# Light_Sensor_-_Teensy.net
KiCad netlist of a schematic drawn in EAGLE
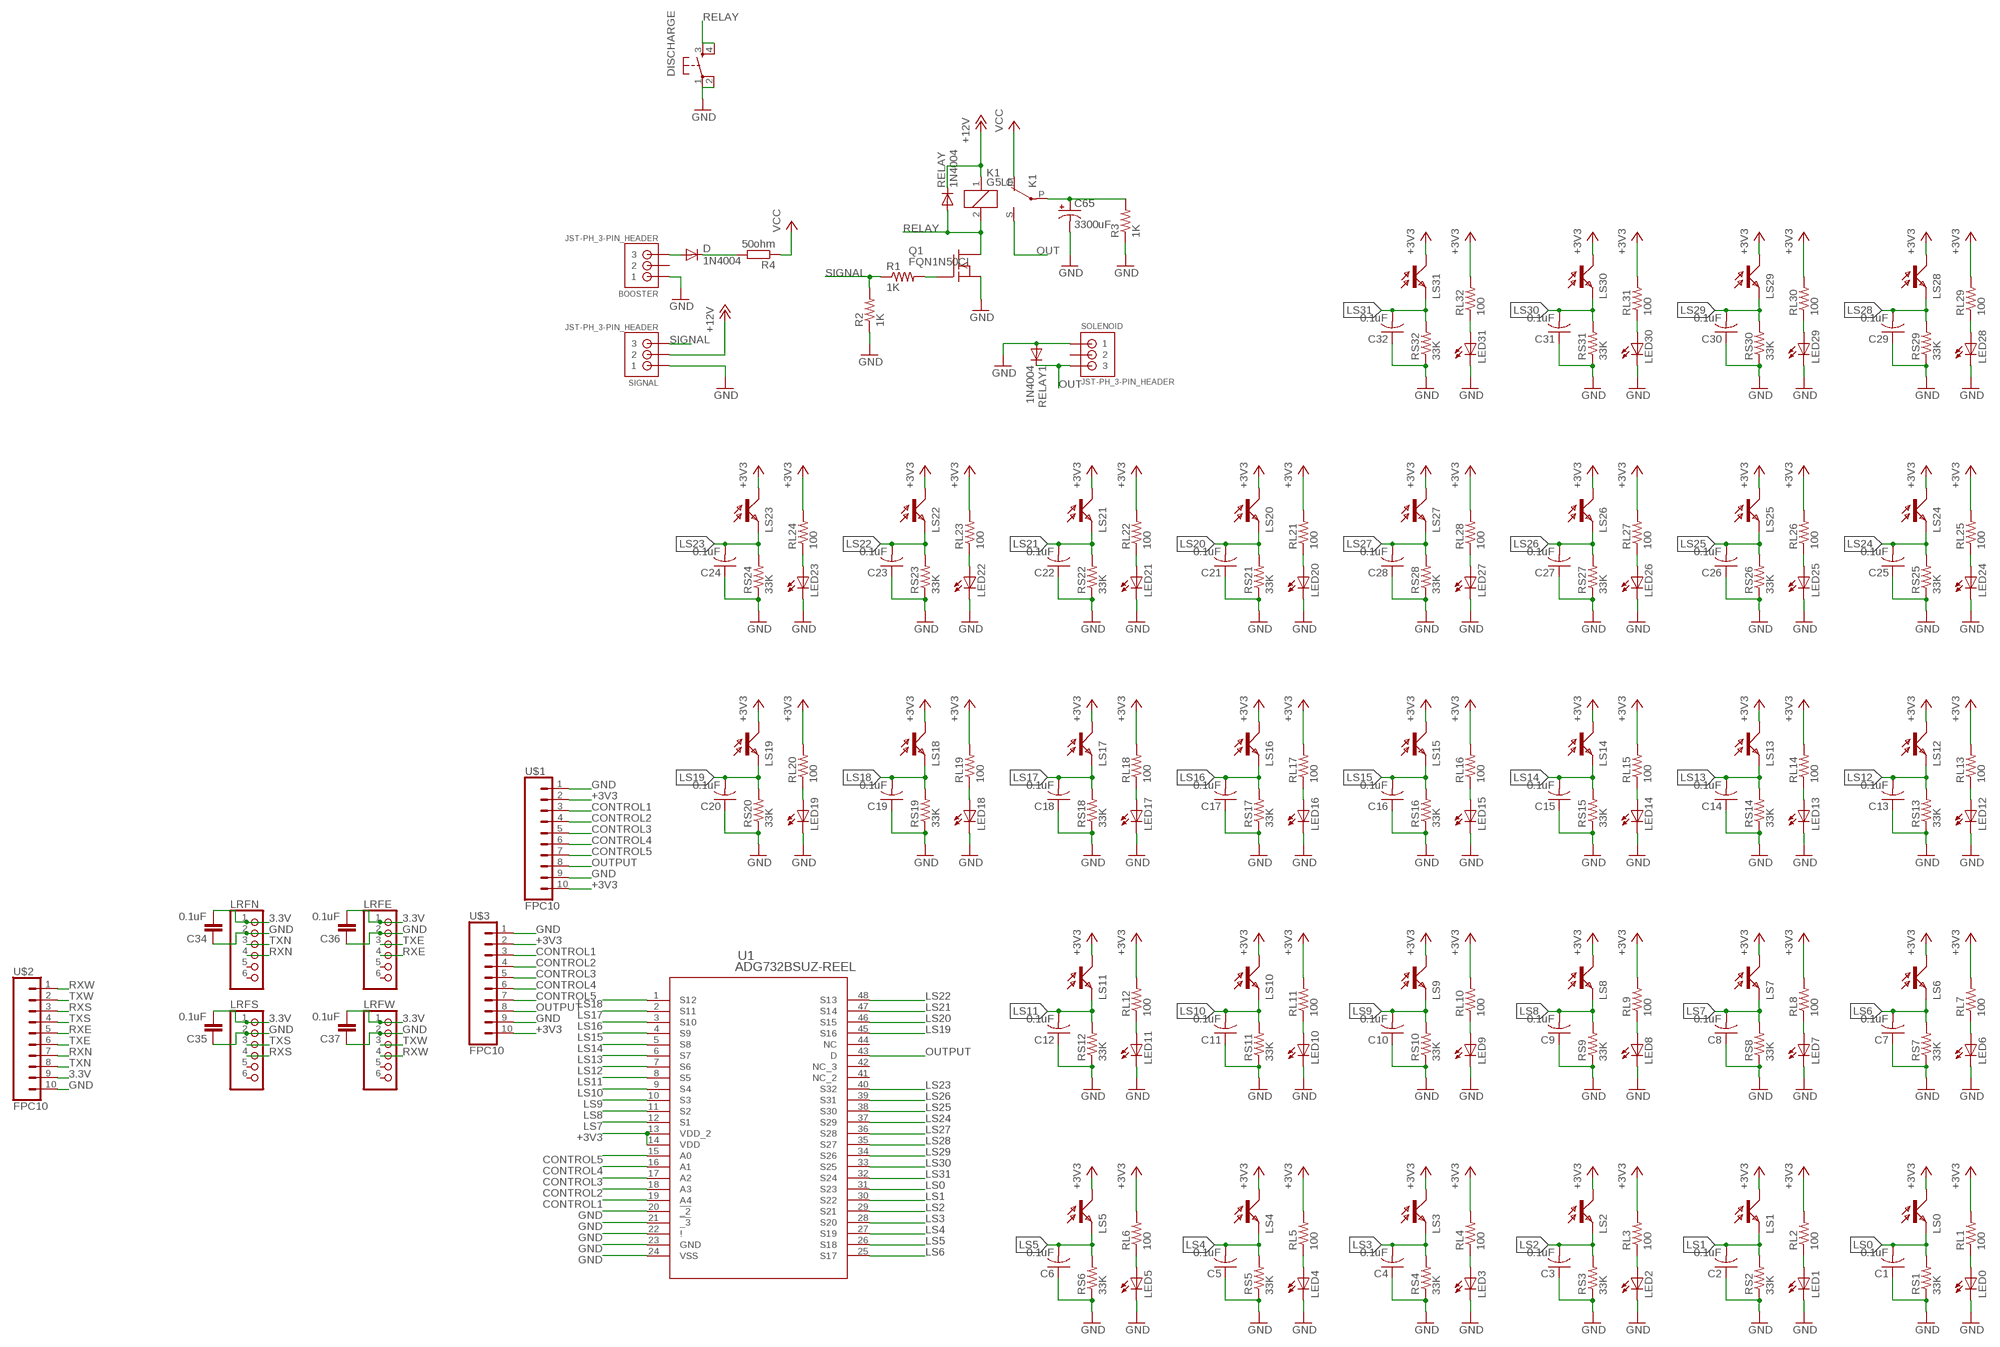
[diagram p0: schematic, sheet 1]

(export (version "E")
  (design (tool "Eeschema 10.0.6"))
  (components
    (comp (ref "BOOSTER")
      (value "JST-PH_3-PIN_HEADER")
      (footprint "eagle-import:JST_B3B-PH_HEADER")
      (libsource (lib "eagle-import") (part "JST-PH_3-PIN_HEADER"))
    )
    (comp (ref "C1")
      (value "0.1uF")
      (footprint "eagle-import:C0603")
      (libsource (lib "eagle-import") (part "C-USC0603"))
    )
    (comp (ref "C2")
      (value "0.1uF")
      (footprint "eagle-import:C0603")
      (libsource (lib "eagle-import") (part "C-USC0603"))
    )
    (comp (ref "C3")
      (value "0.1uF")
      (footprint "eagle-import:C0603")
      (libsource (lib "eagle-import") (part "C-USC0603"))
    )
    (comp (ref "C4")
      (value "0.1uF")
      (footprint "eagle-import:C0603")
      (libsource (lib "eagle-import") (part "C-USC0603"))
    )
    (comp (ref "C5")
      (value "0.1uF")
      (footprint "eagle-import:C0603")
      (libsource (lib "eagle-import") (part "C-USC0603"))
    )
    (comp (ref "C6")
      (value "0.1uF")
      (footprint "eagle-import:C0603")
      (libsource (lib "eagle-import") (part "C-USC0603"))
    )
    (comp (ref "C7")
      (value "0.1uF")
      (footprint "eagle-import:C0603")
      (libsource (lib "eagle-import") (part "C-USC0603"))
    )
    (comp (ref "C8")
      (value "0.1uF")
      (footprint "eagle-import:C0603")
      (libsource (lib "eagle-import") (part "C-USC0603"))
    )
    (comp (ref "C9")
      (value "0.1uF")
      (footprint "eagle-import:C0603")
      (libsource (lib "eagle-import") (part "C-USC0603"))
    )
    (comp (ref "C10")
      (value "0.1uF")
      (footprint "eagle-import:C0603")
      (libsource (lib "eagle-import") (part "C-USC0603"))
    )
    (comp (ref "C11")
      (value "0.1uF")
      (footprint "eagle-import:C0603")
      (libsource (lib "eagle-import") (part "C-USC0603"))
    )
    (comp (ref "C12")
      (value "0.1uF")
      (footprint "eagle-import:C0603")
      (libsource (lib "eagle-import") (part "C-USC0603"))
    )
    (comp (ref "C13")
      (value "0.1uF")
      (footprint "eagle-import:C0603")
      (libsource (lib "eagle-import") (part "C-USC0603"))
    )
    (comp (ref "C14")
      (value "0.1uF")
      (footprint "eagle-import:C0603")
      (libsource (lib "eagle-import") (part "C-USC0603"))
    )
    (comp (ref "C15")
      (value "0.1uF")
      (footprint "eagle-import:C0603")
      (libsource (lib "eagle-import") (part "C-USC0603"))
    )
    (comp (ref "C16")
      (value "0.1uF")
      (footprint "eagle-import:C0603")
      (libsource (lib "eagle-import") (part "C-USC0603"))
    )
    (comp (ref "C17")
      (value "0.1uF")
      (footprint "eagle-import:C0603")
      (libsource (lib "eagle-import") (part "C-USC0603"))
    )
    (comp (ref "C18")
      (value "0.1uF")
      (footprint "eagle-import:C0603")
      (libsource (lib "eagle-import") (part "C-USC0603"))
    )
    (comp (ref "C19")
      (value "0.1uF")
      (footprint "eagle-import:C0603")
      (libsource (lib "eagle-import") (part "C-USC0603"))
    )
    (comp (ref "C20")
      (value "0.1uF")
      (footprint "eagle-import:C0603")
      (libsource (lib "eagle-import") (part "C-USC0603"))
    )
    (comp (ref "C21")
      (value "0.1uF")
      (footprint "eagle-import:C0603")
      (libsource (lib "eagle-import") (part "C-USC0603"))
    )
    (comp (ref "C22")
      (value "0.1uF")
      (footprint "eagle-import:C0603")
      (libsource (lib "eagle-import") (part "C-USC0603"))
    )
    (comp (ref "C23")
      (value "0.1uF")
      (footprint "eagle-import:C0603")
      (libsource (lib "eagle-import") (part "C-USC0603"))
    )
    (comp (ref "C24")
      (value "0.1uF")
      (footprint "eagle-import:C0603")
      (libsource (lib "eagle-import") (part "C-USC0603"))
    )
    (comp (ref "C25")
      (value "0.1uF")
      (footprint "eagle-import:C0603")
      (libsource (lib "eagle-import") (part "C-USC0603"))
    )
    (comp (ref "C26")
      (value "0.1uF")
      (footprint "eagle-import:C0603")
      (libsource (lib "eagle-import") (part "C-USC0603"))
    )
    (comp (ref "C27")
      (value "0.1uF")
      (footprint "eagle-import:C0603")
      (libsource (lib "eagle-import") (part "C-USC0603"))
    )
    (comp (ref "C28")
      (value "0.1uF")
      (footprint "eagle-import:C0603")
      (libsource (lib "eagle-import") (part "C-USC0603"))
    )
    (comp (ref "C29")
      (value "0.1uF")
      (footprint "eagle-import:C0603")
      (libsource (lib "eagle-import") (part "C-USC0603"))
    )
    (comp (ref "C30")
      (value "0.1uF")
      (footprint "eagle-import:C0603")
      (libsource (lib "eagle-import") (part "C-USC0603"))
    )
    (comp (ref "C31")
      (value "0.1uF")
      (footprint "eagle-import:C0603")
      (libsource (lib "eagle-import") (part "C-USC0603"))
    )
    (comp (ref "C32")
      (value "0.1uF")
      (footprint "eagle-import:C0603")
      (libsource (lib "eagle-import") (part "C-USC0603"))
    )
    (comp (ref "C34")
      (value "0.1uF")
      (footprint "eagle-import:0603")
      (libsource (lib "eagle-import") (part "0.1UF-0603-25V-(+80/-20%)"))
    )
    (comp (ref "C35")
      (value "0.1uF")
      (footprint "eagle-import:0603")
      (libsource (lib "eagle-import") (part "0.1UF-0603-25V-(+80/-20%)"))
    )
    (comp (ref "C36")
      (value "0.1uF")
      (footprint "eagle-import:0603")
      (libsource (lib "eagle-import") (part "0.1UF-0603-25V-(+80/-20%)"))
    )
    (comp (ref "C37")
      (value "0.1uF")
      (footprint "eagle-import:0603")
      (libsource (lib "eagle-import") (part "0.1UF-0603-25V-(+80/-20%)"))
    )
    (comp (ref "C65")
      (value "3300uF")
      (footprint "eagle-import:EB22,5D")
      (libsource (lib "eagle-import") (part "CPOL-USE10-22.5"))
    )
    (comp (ref "D")
      (value "1N4004")
      (footprint "eagle-import:DO41-10")
      (libsource (lib "eagle-import") (part "1N4004"))
    )
    (comp (ref "DISCHARGE")
      (value "TAC_SWITCHPTH")
      (footprint "eagle-import:TACTILE-PTH")
      (libsource (lib "eagle-import") (part "TAC_SWITCHPTH"))
    )
    (comp (ref "K1")
      (value "G5LE")
      (footprint "eagle-import:G5LE")
      (libsource (lib "eagle-import") (part "G5LE"))
    )
    (comp (ref "LED0")
      (value "LEDCHIPLED_0603")
      (footprint "eagle-import:CHIPLED_0603")
      (libsource (lib "eagle-import") (part "LEDCHIPLED_0603"))
    )
    (comp (ref "LED1")
      (value "LEDCHIPLED_0603")
      (footprint "eagle-import:CHIPLED_0603")
      (libsource (lib "eagle-import") (part "LEDCHIPLED_0603"))
    )
    (comp (ref "LED2")
      (value "LEDCHIPLED_0603")
      (footprint "eagle-import:CHIPLED_0603")
      (libsource (lib "eagle-import") (part "LEDCHIPLED_0603"))
    )
    (comp (ref "LED3")
      (value "LEDCHIPLED_0603")
      (footprint "eagle-import:CHIPLED_0603")
      (libsource (lib "eagle-import") (part "LEDCHIPLED_0603"))
    )
    (comp (ref "LED4")
      (value "LEDCHIPLED_0603")
      (footprint "eagle-import:CHIPLED_0603")
      (libsource (lib "eagle-import") (part "LEDCHIPLED_0603"))
    )
    (comp (ref "LED5")
      (value "LEDCHIPLED_0603")
      (footprint "eagle-import:CHIPLED_0603")
      (libsource (lib "eagle-import") (part "LEDCHIPLED_0603"))
    )
    (comp (ref "LED6")
      (value "LEDCHIPLED_0603")
      (footprint "eagle-import:CHIPLED_0603")
      (libsource (lib "eagle-import") (part "LEDCHIPLED_0603"))
    )
    (comp (ref "LED7")
      (value "LEDCHIPLED_0603")
      (footprint "eagle-import:CHIPLED_0603")
      (libsource (lib "eagle-import") (part "LEDCHIPLED_0603"))
    )
    (comp (ref "LED8")
      (value "LEDCHIPLED_0603")
      (footprint "eagle-import:CHIPLED_0603")
      (libsource (lib "eagle-import") (part "LEDCHIPLED_0603"))
    )
    (comp (ref "LED9")
      (value "LEDCHIPLED_0603")
      (footprint "eagle-import:CHIPLED_0603")
      (libsource (lib "eagle-import") (part "LEDCHIPLED_0603"))
    )
    (comp (ref "LED10")
      (value "LEDCHIPLED_0603")
      (footprint "eagle-import:CHIPLED_0603")
      (libsource (lib "eagle-import") (part "LEDCHIPLED_0603"))
    )
    (comp (ref "LED11")
      (value "LEDCHIPLED_0603")
      (footprint "eagle-import:CHIPLED_0603")
      (libsource (lib "eagle-import") (part "LEDCHIPLED_0603"))
    )
    (comp (ref "LED12")
      (value "LEDCHIPLED_0603")
      (footprint "eagle-import:CHIPLED_0603")
      (libsource (lib "eagle-import") (part "LEDCHIPLED_0603"))
    )
    (comp (ref "LED13")
      (value "LEDCHIPLED_0603")
      (footprint "eagle-import:CHIPLED_0603")
      (libsource (lib "eagle-import") (part "LEDCHIPLED_0603"))
    )
    (comp (ref "LED14")
      (value "LEDCHIPLED_0603")
      (footprint "eagle-import:CHIPLED_0603")
      (libsource (lib "eagle-import") (part "LEDCHIPLED_0603"))
    )
    (comp (ref "LED15")
      (value "LEDCHIPLED_0603")
      (footprint "eagle-import:CHIPLED_0603")
      (libsource (lib "eagle-import") (part "LEDCHIPLED_0603"))
    )
    (comp (ref "LED16")
      (value "LEDCHIPLED_0603")
      (footprint "eagle-import:CHIPLED_0603")
      (libsource (lib "eagle-import") (part "LEDCHIPLED_0603"))
    )
    (comp (ref "LED17")
      (value "LEDCHIPLED_0603")
      (footprint "eagle-import:CHIPLED_0603")
      (libsource (lib "eagle-import") (part "LEDCHIPLED_0603"))
    )
    (comp (ref "LED18")
      (value "LEDCHIPLED_0603")
      (footprint "eagle-import:CHIPLED_0603")
      (libsource (lib "eagle-import") (part "LEDCHIPLED_0603"))
    )
    (comp (ref "LED19")
      (value "LEDCHIPLED_0603")
      (footprint "eagle-import:CHIPLED_0603")
      (libsource (lib "eagle-import") (part "LEDCHIPLED_0603"))
    )
    (comp (ref "LED20")
      (value "LEDCHIPLED_0603")
      (footprint "eagle-import:CHIPLED_0603")
      (libsource (lib "eagle-import") (part "LEDCHIPLED_0603"))
    )
    (comp (ref "LED21")
      (value "LEDCHIPLED_0603")
      (footprint "eagle-import:CHIPLED_0603")
      (libsource (lib "eagle-import") (part "LEDCHIPLED_0603"))
    )
    (comp (ref "LED22")
      (value "LEDCHIPLED_0603")
      (footprint "eagle-import:CHIPLED_0603")
      (libsource (lib "eagle-import") (part "LEDCHIPLED_0603"))
    )
    (comp (ref "LED23")
      (value "LEDCHIPLED_0603")
      (footprint "eagle-import:CHIPLED_0603")
      (libsource (lib "eagle-import") (part "LEDCHIPLED_0603"))
    )
    (comp (ref "LED24")
      (value "LEDCHIPLED_0603")
      (footprint "eagle-import:CHIPLED_0603")
      (libsource (lib "eagle-import") (part "LEDCHIPLED_0603"))
    )
    (comp (ref "LED25")
      (value "LEDCHIPLED_0603")
      (footprint "eagle-import:CHIPLED_0603")
      (libsource (lib "eagle-import") (part "LEDCHIPLED_0603"))
    )
    (comp (ref "LED26")
      (value "LEDCHIPLED_0603")
      (footprint "eagle-import:CHIPLED_0603")
      (libsource (lib "eagle-import") (part "LEDCHIPLED_0603"))
    )
    (comp (ref "LED27")
      (value "LEDCHIPLED_0603")
      (footprint "eagle-import:CHIPLED_0603")
      (libsource (lib "eagle-import") (part "LEDCHIPLED_0603"))
    )
    (comp (ref "LED28")
      (value "LEDCHIPLED_0603")
      (footprint "eagle-import:CHIPLED_0603")
      (libsource (lib "eagle-import") (part "LEDCHIPLED_0603"))
    )
    (comp (ref "LED29")
      (value "LEDCHIPLED_0603")
      (footprint "eagle-import:CHIPLED_0603")
      (libsource (lib "eagle-import") (part "LEDCHIPLED_0603"))
    )
    (comp (ref "LED30")
      (value "LEDCHIPLED_0603")
      (footprint "eagle-import:CHIPLED_0603")
      (libsource (lib "eagle-import") (part "LEDCHIPLED_0603"))
    )
    (comp (ref "LED31")
      (value "LEDCHIPLED_0603")
      (footprint "eagle-import:CHIPLED_0603")
      (libsource (lib "eagle-import") (part "LEDCHIPLED_0603"))
    )
    (comp (ref "LRFE")
      (value "PINHD-1X6")
      (footprint "eagle-import:1X06")
      (libsource (lib "eagle-import") (part "PINHD-1X6"))
    )
    (comp (ref "LRFN")
      (value "PINHD-1X6")
      (footprint "eagle-import:1X06")
      (libsource (lib "eagle-import") (part "PINHD-1X6"))
    )
    (comp (ref "LRFS")
      (value "PINHD-1X6")
      (footprint "eagle-import:1X06")
      (libsource (lib "eagle-import") (part "PINHD-1X6"))
    )
    (comp (ref "LRFW")
      (value "PINHD-1X6")
      (footprint "eagle-import:1X06")
      (libsource (lib "eagle-import") (part "PINHD-1X6"))
    )
    (comp (ref "LS0")
      (value "ALS")
      (footprint "eagle-import:SMD")
      (libsource (lib "eagle-import") (part "ALS"))
    )
    (comp (ref "LS1")
      (value "ALS")
      (footprint "eagle-import:SMD")
      (libsource (lib "eagle-import") (part "ALS"))
    )
    (comp (ref "LS2")
      (value "ALS")
      (footprint "eagle-import:SMD")
      (libsource (lib "eagle-import") (part "ALS"))
    )
    (comp (ref "LS3")
      (value "ALS")
      (footprint "eagle-import:SMD")
      (libsource (lib "eagle-import") (part "ALS"))
    )
    (comp (ref "LS4")
      (value "ALS")
      (footprint "eagle-import:SMD")
      (libsource (lib "eagle-import") (part "ALS"))
    )
    (comp (ref "LS5")
      (value "ALS")
      (footprint "eagle-import:SMD")
      (libsource (lib "eagle-import") (part "ALS"))
    )
    (comp (ref "LS6")
      (value "ALS")
      (footprint "eagle-import:SMD")
      (libsource (lib "eagle-import") (part "ALS"))
    )
    (comp (ref "LS7")
      (value "ALS")
      (footprint "eagle-import:SMD")
      (libsource (lib "eagle-import") (part "ALS"))
    )
    (comp (ref "LS8")
      (value "ALS")
      (footprint "eagle-import:SMD")
      (libsource (lib "eagle-import") (part "ALS"))
    )
    (comp (ref "LS9")
      (value "ALS")
      (footprint "eagle-import:SMD")
      (libsource (lib "eagle-import") (part "ALS"))
    )
    (comp (ref "LS10")
      (value "ALS")
      (footprint "eagle-import:SMD")
      (libsource (lib "eagle-import") (part "ALS"))
    )
    (comp (ref "LS11")
      (value "ALS")
      (footprint "eagle-import:SMD")
      (libsource (lib "eagle-import") (part "ALS"))
    )
    (comp (ref "LS12")
      (value "ALS")
      (footprint "eagle-import:SMD")
      (libsource (lib "eagle-import") (part "ALS"))
    )
    (comp (ref "LS13")
      (value "ALS")
      (footprint "eagle-import:SMD")
      (libsource (lib "eagle-import") (part "ALS"))
    )
    (comp (ref "LS14")
      (value "ALS")
      (footprint "eagle-import:SMD")
      (libsource (lib "eagle-import") (part "ALS"))
    )
    (comp (ref "LS15")
      (value "ALS")
      (footprint "eagle-import:SMD")
      (libsource (lib "eagle-import") (part "ALS"))
    )
    (comp (ref "LS16")
      (value "ALS")
      (footprint "eagle-import:SMD")
      (libsource (lib "eagle-import") (part "ALS"))
    )
    (comp (ref "LS17")
      (value "ALS")
      (footprint "eagle-import:SMD")
      (libsource (lib "eagle-import") (part "ALS"))
    )
    (comp (ref "LS18")
      (value "ALS")
      (footprint "eagle-import:SMD")
      (libsource (lib "eagle-import") (part "ALS"))
    )
    (comp (ref "LS19")
      (value "ALS")
      (footprint "eagle-import:SMD")
      (libsource (lib "eagle-import") (part "ALS"))
    )
    (comp (ref "LS20")
      (value "ALS")
      (footprint "eagle-import:SMD")
      (libsource (lib "eagle-import") (part "ALS"))
    )
    (comp (ref "LS21")
      (value "ALS")
      (footprint "eagle-import:SMD")
      (libsource (lib "eagle-import") (part "ALS"))
    )
    (comp (ref "LS22")
      (value "ALS")
      (footprint "eagle-import:SMD")
      (libsource (lib "eagle-import") (part "ALS"))
    )
    (comp (ref "LS23")
      (value "ALS")
      (footprint "eagle-import:SMD")
      (libsource (lib "eagle-import") (part "ALS"))
    )
    (comp (ref "LS24")
      (value "ALS")
      (footprint "eagle-import:SMD")
      (libsource (lib "eagle-import") (part "ALS"))
    )
    (comp (ref "LS25")
      (value "ALS")
      (footprint "eagle-import:SMD")
      (libsource (lib "eagle-import") (part "ALS"))
    )
    (comp (ref "LS26")
      (value "ALS")
      (footprint "eagle-import:SMD")
      (libsource (lib "eagle-import") (part "ALS"))
    )
    (comp (ref "LS27")
      (value "ALS")
      (footprint "eagle-import:SMD")
      (libsource (lib "eagle-import") (part "ALS"))
    )
    (comp (ref "LS28")
      (value "ALS")
      (footprint "eagle-import:SMD")
      (libsource (lib "eagle-import") (part "ALS"))
    )
    (comp (ref "LS29")
      (value "ALS")
      (footprint "eagle-import:SMD")
      (libsource (lib "eagle-import") (part "ALS"))
    )
    (comp (ref "LS30")
      (value "ALS")
      (footprint "eagle-import:SMD")
      (libsource (lib "eagle-import") (part "ALS"))
    )
    (comp (ref "LS31")
      (value "ALS")
      (footprint "eagle-import:SMD")
      (libsource (lib "eagle-import") (part "ALS"))
    )
    (comp (ref "Q1")
      (value "FQN1N50CI")
      (footprint "eagle-import:TO92-INLINE")
      (libsource (lib "eagle-import") (part "FQN1N50CI"))
    )
    (comp (ref "R1")
      (value "1K")
      (footprint "eagle-import:AXIAL-0.3")
      (libsource (lib "eagle-import") (part "1KOHM-1/4W-1%(PTH)"))
    )
    (comp (ref "R2")
      (value "1K")
      (footprint "eagle-import:AXIAL-0.3")
      (libsource (lib "eagle-import") (part "1KOHM-1/4W-1%(PTH)"))
    )
    (comp (ref "R3")
      (value "1K")
      (footprint "eagle-import:AXIAL-0.3")
      (libsource (lib "eagle-import") (part "1KOHM-1/4W-1%(PTH)"))
    )
    (comp (ref "R4")
      (value "50ohm")
      (footprint "eagle-import:0207_10")
      (libsource (lib "eagle-import") (part "R0207/10"))
    )
    (comp (ref "RELAY")
      (value "1N4004")
      (footprint "eagle-import:DO41-10")
      (libsource (lib "eagle-import") (part "1N4004"))
    )
    (comp (ref "RELAY1")
      (value "1N4004")
      (footprint "eagle-import:DO41-10")
      (libsource (lib "eagle-import") (part "1N4004"))
    )
    (comp (ref "RL1")
      (value "100")
      (footprint "eagle-import:R0603")
      (libsource (lib "eagle-import") (part "R-US_R0603"))
    )
    (comp (ref "RL2")
      (value "100")
      (footprint "eagle-import:R0603")
      (libsource (lib "eagle-import") (part "R-US_R0603"))
    )
    (comp (ref "RL3")
      (value "100")
      (footprint "eagle-import:R0603")
      (libsource (lib "eagle-import") (part "R-US_R0603"))
    )
    (comp (ref "RL4")
      (value "100")
      (footprint "eagle-import:R0603")
      (libsource (lib "eagle-import") (part "R-US_R0603"))
    )
    (comp (ref "RL5")
      (value "100")
      (footprint "eagle-import:R0603")
      (libsource (lib "eagle-import") (part "R-US_R0603"))
    )
    (comp (ref "RL6")
      (value "100")
      (footprint "eagle-import:R0603")
      (libsource (lib "eagle-import") (part "R-US_R0603"))
    )
    (comp (ref "RL7")
      (value "100")
      (footprint "eagle-import:R0603")
      (libsource (lib "eagle-import") (part "R-US_R0603"))
    )
    (comp (ref "RL8")
      (value "100")
      (footprint "eagle-import:R0603")
      (libsource (lib "eagle-import") (part "R-US_R0603"))
    )
    (comp (ref "RL9")
      (value "100")
      (footprint "eagle-import:R0603")
      (libsource (lib "eagle-import") (part "R-US_R0603"))
    )
    (comp (ref "RL10")
      (value "100")
      (footprint "eagle-import:R0603")
      (libsource (lib "eagle-import") (part "R-US_R0603"))
    )
    (comp (ref "RL11")
      (value "100")
      (footprint "eagle-import:R0603")
      (libsource (lib "eagle-import") (part "R-US_R0603"))
    )
    (comp (ref "RL12")
      (value "100")
      (footprint "eagle-import:R0603")
      (libsource (lib "eagle-import") (part "R-US_R0603"))
    )
    (comp (ref "RL13")
      (value "100")
      (footprint "eagle-import:R0603")
      (libsource (lib "eagle-import") (part "R-US_R0603"))
    )
    (comp (ref "RL14")
      (value "100")
      (footprint "eagle-import:R0603")
      (libsource (lib "eagle-import") (part "R-US_R0603"))
    )
    (comp (ref "RL15")
      (value "100")
      (footprint "eagle-import:R0603")
      (libsource (lib "eagle-import") (part "R-US_R0603"))
    )
    (comp (ref "RL16")
      (value "100")
      (footprint "eagle-import:R0603")
      (libsource (lib "eagle-import") (part "R-US_R0603"))
    )
    (comp (ref "RL17")
      (value "100")
      (footprint "eagle-import:R0603")
      (libsource (lib "eagle-import") (part "R-US_R0603"))
    )
    (comp (ref "RL18")
      (value "100")
      (footprint "eagle-import:R0603")
      (libsource (lib "eagle-import") (part "R-US_R0603"))
    )
    (comp (ref "RL19")
      (value "100")
      (footprint "eagle-import:R0603")
      (libsource (lib "eagle-import") (part "R-US_R0603"))
    )
    (comp (ref "RL20")
      (value "100")
      (footprint "eagle-import:R0603")
      (libsource (lib "eagle-import") (part "R-US_R0603"))
    )
    (comp (ref "RL21")
      (value "100")
      (footprint "eagle-import:R0603")
      (libsource (lib "eagle-import") (part "R-US_R0603"))
    )
    (comp (ref "RL22")
      (value "100")
      (footprint "eagle-import:R0603")
      (libsource (lib "eagle-import") (part "R-US_R0603"))
    )
    (comp (ref "RL23")
      (value "100")
      (footprint "eagle-import:R0603")
      (libsource (lib "eagle-import") (part "R-US_R0603"))
    )
    (comp (ref "RL24")
      (value "100")
      (footprint "eagle-import:R0603")
      (libsource (lib "eagle-import") (part "R-US_R0603"))
    )
    (comp (ref "RL25")
      (value "100")
      (footprint "eagle-import:R0603")
      (libsource (lib "eagle-import") (part "R-US_R0603"))
    )
    (comp (ref "RL26")
      (value "100")
      (footprint "eagle-import:R0603")
      (libsource (lib "eagle-import") (part "R-US_R0603"))
    )
    (comp (ref "RL27")
      (value "100")
      (footprint "eagle-import:R0603")
      (libsource (lib "eagle-import") (part "R-US_R0603"))
    )
    (comp (ref "RL28")
      (value "100")
      (footprint "eagle-import:R0603")
      (libsource (lib "eagle-import") (part "R-US_R0603"))
    )
    (comp (ref "RL29")
      (value "100")
      (footprint "eagle-import:R0603")
      (libsource (lib "eagle-import") (part "R-US_R0603"))
    )
    (comp (ref "RL30")
      (value "100")
      (footprint "eagle-import:R0603")
      (libsource (lib "eagle-import") (part "R-US_R0603"))
    )
    (comp (ref "RL31")
      (value "100")
      (footprint "eagle-import:R0603")
      (libsource (lib "eagle-import") (part "R-US_R0603"))
    )
    (comp (ref "RL32")
      (value "100")
      (footprint "eagle-import:R0603")
      (libsource (lib "eagle-import") (part "R-US_R0603"))
    )
    (comp (ref "RS1")
      (value "33K")
      (footprint "eagle-import:R0603")
      (libsource (lib "eagle-import") (part "R-US_R0603"))
    )
    (comp (ref "RS2")
      (value "33K")
      (footprint "eagle-import:R0603")
      (libsource (lib "eagle-import") (part "R-US_R0603"))
    )
    (comp (ref "RS3")
      (value "33K")
      (footprint "eagle-import:R0603")
      (libsource (lib "eagle-import") (part "R-US_R0603"))
    )
    (comp (ref "RS4")
      (value "33K")
      (footprint "eagle-import:R0603")
      (libsource (lib "eagle-import") (part "R-US_R0603"))
    )
    (comp (ref "RS5")
      (value "33K")
      (footprint "eagle-import:R0603")
      (libsource (lib "eagle-import") (part "R-US_R0603"))
    )
    (comp (ref "RS6")
      (value "33K")
      (footprint "eagle-import:R0603")
      (libsource (lib "eagle-import") (part "R-US_R0603"))
    )
    (comp (ref "RS7")
      (value "33K")
      (footprint "eagle-import:R0603")
      (libsource (lib "eagle-import") (part "R-US_R0603"))
    )
    (comp (ref "RS8")
      (value "33K")
      (footprint "eagle-import:R0603")
      (libsource (lib "eagle-import") (part "R-US_R0603"))
    )
    (comp (ref "RS9")
      (value "33K")
      (footprint "eagle-import:R0603")
      (libsource (lib "eagle-import") (part "R-US_R0603"))
    )
    (comp (ref "RS10")
      (value "33K")
      (footprint "eagle-import:R0603")
      (libsource (lib "eagle-import") (part "R-US_R0603"))
    )
    (comp (ref "RS11")
      (value "33K")
      (footprint "eagle-import:R0603")
      (libsource (lib "eagle-import") (part "R-US_R0603"))
    )
    (comp (ref "RS12")
      (value "33K")
      (footprint "eagle-import:R0603")
      (libsource (lib "eagle-import") (part "R-US_R0603"))
    )
    (comp (ref "RS13")
      (value "33K")
      (footprint "eagle-import:R0603")
      (libsource (lib "eagle-import") (part "R-US_R0603"))
    )
    (comp (ref "RS14")
      (value "33K")
      (footprint "eagle-import:R0603")
      (libsource (lib "eagle-import") (part "R-US_R0603"))
    )
    (comp (ref "RS15")
      (value "33K")
      (footprint "eagle-import:R0603")
      (libsource (lib "eagle-import") (part "R-US_R0603"))
    )
    (comp (ref "RS16")
      (value "33K")
      (footprint "eagle-import:R0603")
      (libsource (lib "eagle-import") (part "R-US_R0603"))
    )
    (comp (ref "RS17")
      (value "33K")
      (footprint "eagle-import:R0603")
      (libsource (lib "eagle-import") (part "R-US_R0603"))
    )
    (comp (ref "RS18")
      (value "33K")
      (footprint "eagle-import:R0603")
      (libsource (lib "eagle-import") (part "R-US_R0603"))
    )
    (comp (ref "RS19")
      (value "33K")
      (footprint "eagle-import:R0603")
      (libsource (lib "eagle-import") (part "R-US_R0603"))
    )
    (comp (ref "RS20")
      (value "33K")
      (footprint "eagle-import:R0603")
      (libsource (lib "eagle-import") (part "R-US_R0603"))
    )
    (comp (ref "RS21")
      (value "33K")
      (footprint "eagle-import:R0603")
      (libsource (lib "eagle-import") (part "R-US_R0603"))
    )
    (comp (ref "RS22")
      (value "33K")
      (footprint "eagle-import:R0603")
      (libsource (lib "eagle-import") (part "R-US_R0603"))
    )
    (comp (ref "RS23")
      (value "33K")
      (footprint "eagle-import:R0603")
      (libsource (lib "eagle-import") (part "R-US_R0603"))
    )
    (comp (ref "RS24")
      (value "33K")
      (footprint "eagle-import:R0603")
      (libsource (lib "eagle-import") (part "R-US_R0603"))
    )
    (comp (ref "RS25")
      (value "33K")
      (footprint "eagle-import:R0603")
      (libsource (lib "eagle-import") (part "R-US_R0603"))
    )
    (comp (ref "RS26")
      (value "33K")
      (footprint "eagle-import:R0603")
      (libsource (lib "eagle-import") (part "R-US_R0603"))
    )
    (comp (ref "RS27")
      (value "33K")
      (footprint "eagle-import:R0603")
      (libsource (lib "eagle-import") (part "R-US_R0603"))
    )
    (comp (ref "RS28")
      (value "33K")
      (footprint "eagle-import:R0603")
      (libsource (lib "eagle-import") (part "R-US_R0603"))
    )
    (comp (ref "RS29")
      (value "33K")
      (footprint "eagle-import:R0603")
      (libsource (lib "eagle-import") (part "R-US_R0603"))
    )
    (comp (ref "RS30")
      (value "33K")
      (footprint "eagle-import:R0603")
      (libsource (lib "eagle-import") (part "R-US_R0603"))
    )
    (comp (ref "RS31")
      (value "33K")
      (footprint "eagle-import:R0603")
      (libsource (lib "eagle-import") (part "R-US_R0603"))
    )
    (comp (ref "RS32")
      (value "33K")
      (footprint "eagle-import:R0603")
      (libsource (lib "eagle-import") (part "R-US_R0603"))
    )
    (comp (ref "SIGNAL")
      (value "JST-PH_3-PIN_HEADER")
      (footprint "eagle-import:JST_B3B-PH_HEADER")
      (libsource (lib "eagle-import") (part "JST-PH_3-PIN_HEADER"))
    )
    (comp (ref "SOLENOID")
      (value "JST-PH_3-PIN_HEADER")
      (footprint "eagle-import:JST_B3B-PH_HEADER")
      (libsource (lib "eagle-import") (part "JST-PH_3-PIN_HEADER"))
    )
    (comp (ref "U$1")
      (value "FPC10")
      (footprint "eagle-import:FPC10")
      (libsource (lib "eagle-import") (part "FPC10"))
    )
    (comp (ref "U$2")
      (value "FPC10")
      (footprint "eagle-import:FPC10")
      (libsource (lib "eagle-import") (part "FPC10"))
    )
    (comp (ref "U$3")
      (value "FPC10")
      (footprint "eagle-import:FPC10")
      (libsource (lib "eagle-import") (part "FPC10"))
    )
    (comp (ref "U1")
      (value "ADG732BSUZ-REEL")
      (footprint "eagle-import:SU_48")
      (fields (field (name "MANUFACTURER_PART_NUMBER") "ADG732BSUZREEL"))
      (libsource (lib "eagle-import") (part "ADG732BSUZ-REEL"))
    )
  )
  (nets
    (net (code "1") (name "+3V3") (class "Default")
      (node (ref "LS0") (pin "C") (pinfunction "C_C") (pintype "passive"))
      (node (ref "LS1") (pin "C") (pinfunction "C_C") (pintype "passive"))
      (node (ref "LS10") (pin "C") (pinfunction "C_C") (pintype "passive"))
      (node (ref "LS11") (pin "C") (pinfunction "C_C") (pintype "passive"))
      (node (ref "LS12") (pin "C") (pinfunction "C_C") (pintype "passive"))
      (node (ref "LS13") (pin "C") (pinfunction "C_C") (pintype "passive"))
      (node (ref "LS14") (pin "C") (pinfunction "C_C") (pintype "passive"))
      (node (ref "LS15") (pin "C") (pinfunction "C_C") (pintype "passive"))
      (node (ref "LS16") (pin "C") (pinfunction "C_C") (pintype "passive"))
      (node (ref "LS17") (pin "C") (pinfunction "C_C") (pintype "passive"))
      (node (ref "LS18") (pin "C") (pinfunction "C_C") (pintype "passive"))
      (node (ref "LS19") (pin "C") (pinfunction "C_C") (pintype "passive"))
      (node (ref "LS2") (pin "C") (pinfunction "C_C") (pintype "passive"))
      (node (ref "LS20") (pin "C") (pinfunction "C_C") (pintype "passive"))
      (node (ref "LS21") (pin "C") (pinfunction "C_C") (pintype "passive"))
      (node (ref "LS22") (pin "C") (pinfunction "C_C") (pintype "passive"))
      (node (ref "LS23") (pin "C") (pinfunction "C_C") (pintype "passive"))
      (node (ref "LS24") (pin "C") (pinfunction "C_C") (pintype "passive"))
      (node (ref "LS25") (pin "C") (pinfunction "C_C") (pintype "passive"))
      (node (ref "LS26") (pin "C") (pinfunction "C_C") (pintype "passive"))
      (node (ref "LS27") (pin "C") (pinfunction "C_C") (pintype "passive"))
      (node (ref "LS28") (pin "C") (pinfunction "C_C") (pintype "passive"))
      (node (ref "LS29") (pin "C") (pinfunction "C_C") (pintype "passive"))
      (node (ref "LS3") (pin "C") (pinfunction "C_C") (pintype "passive"))
      (node (ref "LS30") (pin "C") (pinfunction "C_C") (pintype "passive"))
      (node (ref "LS31") (pin "C") (pinfunction "C_C") (pintype "passive"))
      (node (ref "LS4") (pin "C") (pinfunction "C_C") (pintype "passive"))
      (node (ref "LS5") (pin "C") (pinfunction "C_C") (pintype "passive"))
      (node (ref "LS6") (pin "C") (pinfunction "C_C") (pintype "passive"))
      (node (ref "LS7") (pin "C") (pinfunction "C_C") (pintype "passive"))
      (node (ref "LS8") (pin "C") (pinfunction "C_C") (pintype "passive"))
      (node (ref "LS9") (pin "C") (pinfunction "C_C") (pintype "passive"))
      (node (ref "RL1") (pin "2") (pinfunction "2_2") (pintype "passive"))
      (node (ref "RL10") (pin "2") (pinfunction "2_2") (pintype "passive"))
      (node (ref "RL11") (pin "2") (pinfunction "2_2") (pintype "passive"))
      (node (ref "RL12") (pin "2") (pinfunction "2_2") (pintype "passive"))
      (node (ref "RL13") (pin "2") (pinfunction "2_2") (pintype "passive"))
      (node (ref "RL14") (pin "2") (pinfunction "2_2") (pintype "passive"))
      (node (ref "RL15") (pin "2") (pinfunction "2_2") (pintype "passive"))
      (node (ref "RL16") (pin "2") (pinfunction "2_2") (pintype "passive"))
      (node (ref "RL17") (pin "2") (pinfunction "2_2") (pintype "passive"))
      (node (ref "RL18") (pin "2") (pinfunction "2_2") (pintype "passive"))
      (node (ref "RL19") (pin "2") (pinfunction "2_2") (pintype "passive"))
      (node (ref "RL2") (pin "2") (pinfunction "2_2") (pintype "passive"))
      (node (ref "RL20") (pin "2") (pinfunction "2_2") (pintype "passive"))
      (node (ref "RL21") (pin "2") (pinfunction "2_2") (pintype "passive"))
      (node (ref "RL22") (pin "2") (pinfunction "2_2") (pintype "passive"))
      (node (ref "RL23") (pin "2") (pinfunction "2_2") (pintype "passive"))
      (node (ref "RL24") (pin "2") (pinfunction "2_2") (pintype "passive"))
      (node (ref "RL25") (pin "2") (pinfunction "2_2") (pintype "passive"))
      (node (ref "RL26") (pin "2") (pinfunction "2_2") (pintype "passive"))
      (node (ref "RL27") (pin "2") (pinfunction "2_2") (pintype "passive"))
      (node (ref "RL28") (pin "2") (pinfunction "2_2") (pintype "passive"))
      (node (ref "RL29") (pin "2") (pinfunction "2_2") (pintype "passive"))
      (node (ref "RL3") (pin "2") (pinfunction "2_2") (pintype "passive"))
      (node (ref "RL30") (pin "2") (pinfunction "2_2") (pintype "passive"))
      (node (ref "RL31") (pin "2") (pinfunction "2_2") (pintype "passive"))
      (node (ref "RL32") (pin "2") (pinfunction "2_2") (pintype "passive"))
      (node (ref "RL4") (pin "2") (pinfunction "2_2") (pintype "passive"))
      (node (ref "RL5") (pin "2") (pinfunction "2_2") (pintype "passive"))
      (node (ref "RL6") (pin "2") (pinfunction "2_2") (pintype "passive"))
      (node (ref "RL7") (pin "2") (pinfunction "2_2") (pintype "passive"))
      (node (ref "RL8") (pin "2") (pinfunction "2_2") (pintype "passive"))
      (node (ref "RL9") (pin "2") (pinfunction "2_2") (pintype "passive"))
      (node (ref "U$1") (pin "10") (pinfunction "10_10") (pintype "passive"))
      (node (ref "U$1") (pin "2") (pinfunction "2_2") (pintype "passive"))
      (node (ref "U$3") (pin "10") (pinfunction "10_10") (pintype "passive"))
      (node (ref "U$3") (pin "2") (pinfunction "2_2") (pintype "passive"))
      (node (ref "U1") (pin "13") (pinfunction "VDD_2_13") (pintype "power_in"))
      (node (ref "U1") (pin "14") (pinfunction "VDD_14") (pintype "power_in"))
    )
    (net (code "2") (name "+12V") (class "Default")
      (node (ref "K1") (pin "1") (pinfunction "1_1") (pintype "passive"))
      (node (ref "RELAY") (pin "C") (pinfunction "C_C") (pintype "passive"))
      (node (ref "SIGNAL") (pin "P2") (pinfunction "2_P2") (pintype "bidirectional"))
    )
    (net (code "3") (name "/3.3V") (class "Default")
      (node (ref "C34") (pin "2") (pinfunction "2_2") (pintype "passive"))
      (node (ref "C35") (pin "2") (pinfunction "2_2") (pintype "passive"))
      (node (ref "C36") (pin "2") (pinfunction "2_2") (pintype "passive"))
      (node (ref "C37") (pin "2") (pinfunction "2_2") (pintype "passive"))
      (node (ref "LRFE") (pin "1") (pinfunction "1_1") (pintype "passive"))
      (node (ref "LRFN") (pin "1") (pinfunction "1_1") (pintype "passive"))
      (node (ref "LRFS") (pin "1") (pinfunction "1_1") (pintype "passive"))
      (node (ref "LRFW") (pin "1") (pinfunction "1_1") (pintype "passive"))
      (node (ref "U$2") (pin "9") (pinfunction "9_9") (pintype "passive"))
    )
    (net (code "4") (name "/CONTROL1") (class "Default")
      (node (ref "U$1") (pin "3") (pinfunction "3_3") (pintype "passive"))
      (node (ref "U$3") (pin "3") (pinfunction "3_3") (pintype "passive"))
      (node (ref "U1") (pin "19") (pinfunction "A4_19") (pintype "passive"))
    )
    (net (code "5") (name "/CONTROL2") (class "Default")
      (node (ref "U$1") (pin "4") (pinfunction "4_4") (pintype "passive"))
      (node (ref "U$3") (pin "4") (pinfunction "4_4") (pintype "passive"))
      (node (ref "U1") (pin "18") (pinfunction "A3_18") (pintype "passive"))
    )
    (net (code "6") (name "/CONTROL3") (class "Default")
      (node (ref "U$1") (pin "5") (pinfunction "5_5") (pintype "passive"))
      (node (ref "U$3") (pin "5") (pinfunction "5_5") (pintype "passive"))
      (node (ref "U1") (pin "17") (pinfunction "A2_17") (pintype "passive"))
    )
    (net (code "7") (name "/CONTROL4") (class "Default")
      (node (ref "U$1") (pin "6") (pinfunction "6_6") (pintype "passive"))
      (node (ref "U$3") (pin "6") (pinfunction "6_6") (pintype "passive"))
      (node (ref "U1") (pin "16") (pinfunction "A1_16") (pintype "passive"))
    )
    (net (code "8") (name "/CONTROL5") (class "Default")
      (node (ref "U$1") (pin "7") (pinfunction "7_7") (pintype "passive"))
      (node (ref "U$3") (pin "7") (pinfunction "7_7") (pintype "passive"))
      (node (ref "U1") (pin "15") (pinfunction "A0_15") (pintype "passive"))
    )
    (net (code "9") (name "/OUT") (class "Default")
      (node (ref "K1") (pin "S") (pinfunction "S_S") (pintype "passive"))
      (node (ref "RELAY1") (pin "C") (pinfunction "C_C") (pintype "passive"))
      (node (ref "SOLENOID") (pin "P3") (pinfunction "3_P3") (pintype "bidirectional"))
    )
    (net (code "10") (name "/OUTPUT") (class "Default")
      (node (ref "U$1") (pin "8") (pinfunction "8_8") (pintype "passive"))
      (node (ref "U$3") (pin "8") (pinfunction "8_8") (pintype "passive"))
      (node (ref "U1") (pin "43") (pinfunction "D_43") (pintype "passive"))
    )
    (net (code "11") (name "/RELAY") (class "Default")
      (node (ref "DISCHARGE") (pin "3") (pinfunction "3_3") (pintype "passive"))
      (node (ref "DISCHARGE") (pin "4") (pinfunction "4_4") (pintype "passive"))
      (node (ref "K1") (pin "2") (pinfunction "2_2") (pintype "passive"))
      (node (ref "Q1") (pin "1") (pinfunction "D_1") (pintype "passive"))
      (node (ref "RELAY") (pin "A") (pinfunction "A_A") (pintype "passive"))
    )
    (net (code "12") (name "/RXE") (class "Default")
      (node (ref "LRFE") (pin "4") (pinfunction "4_4") (pintype "passive"))
      (node (ref "U$2") (pin "5") (pinfunction "5_5") (pintype "passive"))
    )
    (net (code "13") (name "/RXN") (class "Default")
      (node (ref "LRFN") (pin "4") (pinfunction "4_4") (pintype "passive"))
      (node (ref "U$2") (pin "7") (pinfunction "7_7") (pintype "passive"))
    )
    (net (code "14") (name "/RXS") (class "Default")
      (node (ref "LRFS") (pin "4") (pinfunction "4_4") (pintype "passive"))
      (node (ref "U$2") (pin "3") (pinfunction "3_3") (pintype "passive"))
    )
    (net (code "15") (name "/RXW") (class "Default")
      (node (ref "LRFW") (pin "4") (pinfunction "4_4") (pintype "passive"))
      (node (ref "U$2") (pin "1") (pinfunction "1_1") (pintype "passive"))
    )
    (net (code "16") (name "/SIGNAL") (class "Default")
      (node (ref "R1") (pin "P$1") (pinfunction "1_P$1") (pintype "passive"))
      (node (ref "R2") (pin "P$2") (pinfunction "2_P$2") (pintype "passive"))
      (node (ref "SIGNAL") (pin "P3") (pinfunction "3_P3") (pintype "bidirectional"))
    )
    (net (code "17") (name "/TXE") (class "Default")
      (node (ref "LRFE") (pin "3") (pinfunction "3_3") (pintype "passive"))
      (node (ref "U$2") (pin "6") (pinfunction "6_6") (pintype "passive"))
    )
    (net (code "18") (name "/TXN") (class "Default")
      (node (ref "LRFN") (pin "3") (pinfunction "3_3") (pintype "passive"))
      (node (ref "U$2") (pin "8") (pinfunction "8_8") (pintype "passive"))
    )
    (net (code "19") (name "/TXS") (class "Default")
      (node (ref "LRFS") (pin "3") (pinfunction "3_3") (pintype "passive"))
      (node (ref "U$2") (pin "4") (pinfunction "4_4") (pintype "passive"))
    )
    (net (code "20") (name "/TXW") (class "Default")
      (node (ref "LRFW") (pin "3") (pinfunction "3_3") (pintype "passive"))
      (node (ref "U$2") (pin "2") (pinfunction "2_2") (pintype "passive"))
    )
    (net (code "21") (name "GND") (class "Default")
      (node (ref "BOOSTER") (pin "P1") (pinfunction "1_P1") (pintype "bidirectional"))
      (node (ref "C1") (pin "1") (pinfunction "1_1") (pintype "passive"))
      (node (ref "C10") (pin "1") (pinfunction "1_1") (pintype "passive"))
      (node (ref "C11") (pin "1") (pinfunction "1_1") (pintype "passive"))
      (node (ref "C12") (pin "1") (pinfunction "1_1") (pintype "passive"))
      (node (ref "C13") (pin "1") (pinfunction "1_1") (pintype "passive"))
      (node (ref "C14") (pin "1") (pinfunction "1_1") (pintype "passive"))
      (node (ref "C15") (pin "1") (pinfunction "1_1") (pintype "passive"))
      (node (ref "C16") (pin "1") (pinfunction "1_1") (pintype "passive"))
      (node (ref "C17") (pin "1") (pinfunction "1_1") (pintype "passive"))
      (node (ref "C18") (pin "1") (pinfunction "1_1") (pintype "passive"))
      (node (ref "C19") (pin "1") (pinfunction "1_1") (pintype "passive"))
      (node (ref "C2") (pin "1") (pinfunction "1_1") (pintype "passive"))
      (node (ref "C20") (pin "1") (pinfunction "1_1") (pintype "passive"))
      (node (ref "C21") (pin "1") (pinfunction "1_1") (pintype "passive"))
      (node (ref "C22") (pin "1") (pinfunction "1_1") (pintype "passive"))
      (node (ref "C23") (pin "1") (pinfunction "1_1") (pintype "passive"))
      (node (ref "C24") (pin "1") (pinfunction "1_1") (pintype "passive"))
      (node (ref "C25") (pin "1") (pinfunction "1_1") (pintype "passive"))
      (node (ref "C26") (pin "1") (pinfunction "1_1") (pintype "passive"))
      (node (ref "C27") (pin "1") (pinfunction "1_1") (pintype "passive"))
      (node (ref "C28") (pin "1") (pinfunction "1_1") (pintype "passive"))
      (node (ref "C29") (pin "1") (pinfunction "1_1") (pintype "passive"))
      (node (ref "C3") (pin "1") (pinfunction "1_1") (pintype "passive"))
      (node (ref "C30") (pin "1") (pinfunction "1_1") (pintype "passive"))
      (node (ref "C31") (pin "1") (pinfunction "1_1") (pintype "passive"))
      (node (ref "C32") (pin "1") (pinfunction "1_1") (pintype "passive"))
      (node (ref "C34") (pin "1") (pinfunction "1_1") (pintype "passive"))
      (node (ref "C35") (pin "1") (pinfunction "1_1") (pintype "passive"))
      (node (ref "C36") (pin "1") (pinfunction "1_1") (pintype "passive"))
      (node (ref "C37") (pin "1") (pinfunction "1_1") (pintype "passive"))
      (node (ref "C4") (pin "1") (pinfunction "1_1") (pintype "passive"))
      (node (ref "C5") (pin "1") (pinfunction "1_1") (pintype "passive"))
      (node (ref "C6") (pin "1") (pinfunction "1_1") (pintype "passive"))
      (node (ref "C65") (pin "-") (pinfunction "-_-") (pintype "passive"))
      (node (ref "C7") (pin "1") (pinfunction "1_1") (pintype "passive"))
      (node (ref "C8") (pin "1") (pinfunction "1_1") (pintype "passive"))
      (node (ref "C9") (pin "1") (pinfunction "1_1") (pintype "passive"))
      (node (ref "DISCHARGE") (pin "1") (pinfunction "1_1") (pintype "passive"))
      (node (ref "DISCHARGE") (pin "2") (pinfunction "2_2") (pintype "passive"))
      (node (ref "LED0") (pin "C") (pinfunction "C_C") (pintype "passive"))
      (node (ref "LED1") (pin "C") (pinfunction "C_C") (pintype "passive"))
      (node (ref "LED10") (pin "C") (pinfunction "C_C") (pintype "passive"))
      (node (ref "LED11") (pin "C") (pinfunction "C_C") (pintype "passive"))
      (node (ref "LED12") (pin "C") (pinfunction "C_C") (pintype "passive"))
      (node (ref "LED13") (pin "C") (pinfunction "C_C") (pintype "passive"))
      (node (ref "LED14") (pin "C") (pinfunction "C_C") (pintype "passive"))
      (node (ref "LED15") (pin "C") (pinfunction "C_C") (pintype "passive"))
      (node (ref "LED16") (pin "C") (pinfunction "C_C") (pintype "passive"))
      (node (ref "LED17") (pin "C") (pinfunction "C_C") (pintype "passive"))
      (node (ref "LED18") (pin "C") (pinfunction "C_C") (pintype "passive"))
      (node (ref "LED19") (pin "C") (pinfunction "C_C") (pintype "passive"))
      (node (ref "LED2") (pin "C") (pinfunction "C_C") (pintype "passive"))
      (node (ref "LED20") (pin "C") (pinfunction "C_C") (pintype "passive"))
      (node (ref "LED21") (pin "C") (pinfunction "C_C") (pintype "passive"))
      (node (ref "LED22") (pin "C") (pinfunction "C_C") (pintype "passive"))
      (node (ref "LED23") (pin "C") (pinfunction "C_C") (pintype "passive"))
      (node (ref "LED24") (pin "C") (pinfunction "C_C") (pintype "passive"))
      (node (ref "LED25") (pin "C") (pinfunction "C_C") (pintype "passive"))
      (node (ref "LED26") (pin "C") (pinfunction "C_C") (pintype "passive"))
      (node (ref "LED27") (pin "C") (pinfunction "C_C") (pintype "passive"))
      (node (ref "LED28") (pin "C") (pinfunction "C_C") (pintype "passive"))
      (node (ref "LED29") (pin "C") (pinfunction "C_C") (pintype "passive"))
      (node (ref "LED3") (pin "C") (pinfunction "C_C") (pintype "passive"))
      (node (ref "LED30") (pin "C") (pinfunction "C_C") (pintype "passive"))
      (node (ref "LED31") (pin "C") (pinfunction "C_C") (pintype "passive"))
      (node (ref "LED4") (pin "C") (pinfunction "C_C") (pintype "passive"))
      (node (ref "LED5") (pin "C") (pinfunction "C_C") (pintype "passive"))
      (node (ref "LED6") (pin "C") (pinfunction "C_C") (pintype "passive"))
      (node (ref "LED7") (pin "C") (pinfunction "C_C") (pintype "passive"))
      (node (ref "LED8") (pin "C") (pinfunction "C_C") (pintype "passive"))
      (node (ref "LED9") (pin "C") (pinfunction "C_C") (pintype "passive"))
      (node (ref "LRFE") (pin "2") (pinfunction "2_2") (pintype "passive"))
      (node (ref "LRFN") (pin "2") (pinfunction "2_2") (pintype "passive"))
      (node (ref "LRFS") (pin "2") (pinfunction "2_2") (pintype "passive"))
      (node (ref "LRFW") (pin "2") (pinfunction "2_2") (pintype "passive"))
      (node (ref "Q1") (pin "3") (pinfunction "S_3") (pintype "passive"))
      (node (ref "R2") (pin "P$1") (pinfunction "1_P$1") (pintype "passive"))
      (node (ref "R3") (pin "P$1") (pinfunction "1_P$1") (pintype "passive"))
      (node (ref "RELAY1") (pin "A") (pinfunction "A_A") (pintype "passive"))
      (node (ref "RS1") (pin "1") (pinfunction "1_1") (pintype "passive"))
      (node (ref "RS10") (pin "1") (pinfunction "1_1") (pintype "passive"))
      (node (ref "RS11") (pin "1") (pinfunction "1_1") (pintype "passive"))
      (node (ref "RS12") (pin "1") (pinfunction "1_1") (pintype "passive"))
      (node (ref "RS13") (pin "1") (pinfunction "1_1") (pintype "passive"))
      (node (ref "RS14") (pin "1") (pinfunction "1_1") (pintype "passive"))
      (node (ref "RS15") (pin "1") (pinfunction "1_1") (pintype "passive"))
      (node (ref "RS16") (pin "1") (pinfunction "1_1") (pintype "passive"))
      (node (ref "RS17") (pin "1") (pinfunction "1_1") (pintype "passive"))
      (node (ref "RS18") (pin "1") (pinfunction "1_1") (pintype "passive"))
      (node (ref "RS19") (pin "1") (pinfunction "1_1") (pintype "passive"))
      (node (ref "RS2") (pin "1") (pinfunction "1_1") (pintype "passive"))
      (node (ref "RS20") (pin "1") (pinfunction "1_1") (pintype "passive"))
      (node (ref "RS21") (pin "1") (pinfunction "1_1") (pintype "passive"))
      (node (ref "RS22") (pin "1") (pinfunction "1_1") (pintype "passive"))
      (node (ref "RS23") (pin "1") (pinfunction "1_1") (pintype "passive"))
      (node (ref "RS24") (pin "1") (pinfunction "1_1") (pintype "passive"))
      (node (ref "RS25") (pin "1") (pinfunction "1_1") (pintype "passive"))
      (node (ref "RS26") (pin "1") (pinfunction "1_1") (pintype "passive"))
      (node (ref "RS27") (pin "1") (pinfunction "1_1") (pintype "passive"))
      (node (ref "RS28") (pin "1") (pinfunction "1_1") (pintype "passive"))
      (node (ref "RS29") (pin "1") (pinfunction "1_1") (pintype "passive"))
      (node (ref "RS3") (pin "1") (pinfunction "1_1") (pintype "passive"))
      (node (ref "RS30") (pin "1") (pinfunction "1_1") (pintype "passive"))
      (node (ref "RS31") (pin "1") (pinfunction "1_1") (pintype "passive"))
      (node (ref "RS32") (pin "1") (pinfunction "1_1") (pintype "passive"))
      (node (ref "RS4") (pin "1") (pinfunction "1_1") (pintype "passive"))
      (node (ref "RS5") (pin "1") (pinfunction "1_1") (pintype "passive"))
      (node (ref "RS6") (pin "1") (pinfunction "1_1") (pintype "passive"))
      (node (ref "RS7") (pin "1") (pinfunction "1_1") (pintype "passive"))
      (node (ref "RS8") (pin "1") (pinfunction "1_1") (pintype "passive"))
      (node (ref "RS9") (pin "1") (pinfunction "1_1") (pintype "passive"))
      (node (ref "SIGNAL") (pin "P1") (pinfunction "1_P1") (pintype "bidirectional"))
      (node (ref "SOLENOID") (pin "P1") (pinfunction "1_P1") (pintype "bidirectional"))
      (node (ref "U$1") (pin "1") (pinfunction "1_1") (pintype "passive"))
      (node (ref "U$1") (pin "9") (pinfunction "9_9") (pintype "passive"))
      (node (ref "U$2") (pin "10") (pinfunction "10_10") (pintype "passive"))
      (node (ref "U$3") (pin "1") (pinfunction "1_1") (pintype "passive"))
      (node (ref "U$3") (pin "9") (pinfunction "9_9") (pintype "passive"))
      (node (ref "U1") (pin "20") (pinfunction "~{_2}_20") (pintype "passive"))
      (node (ref "U1") (pin "21") (pinfunction "~{_3}_21") (pintype "passive"))
      (node (ref "U1") (pin "22") (pinfunction "~_22") (pintype "passive"))
      (node (ref "U1") (pin "23") (pinfunction "GND_23") (pintype "passive"))
      (node (ref "U1") (pin "24") (pinfunction "VSS_24") (pintype "power_in"))
    )
    (net (code "22") (name "LS0") (class "Default")
      (node (ref "C1") (pin "2") (pinfunction "2_2") (pintype "passive"))
      (node (ref "LS0") (pin "E") (pinfunction "E_E") (pintype "passive"))
      (node (ref "RS1") (pin "2") (pinfunction "2_2") (pintype "passive"))
      (node (ref "U1") (pin "31") (pinfunction "S23_31") (pintype "passive"))
    )
    (net (code "23") (name "LS1") (class "Default")
      (node (ref "C2") (pin "2") (pinfunction "2_2") (pintype "passive"))
      (node (ref "LS1") (pin "E") (pinfunction "E_E") (pintype "passive"))
      (node (ref "RS2") (pin "2") (pinfunction "2_2") (pintype "passive"))
      (node (ref "U1") (pin "30") (pinfunction "S22_30") (pintype "passive"))
    )
    (net (code "24") (name "LS2") (class "Default")
      (node (ref "C3") (pin "2") (pinfunction "2_2") (pintype "passive"))
      (node (ref "LS2") (pin "E") (pinfunction "E_E") (pintype "passive"))
      (node (ref "RS3") (pin "2") (pinfunction "2_2") (pintype "passive"))
      (node (ref "U1") (pin "29") (pinfunction "S21_29") (pintype "passive"))
    )
    (net (code "25") (name "LS3") (class "Default")
      (node (ref "C4") (pin "2") (pinfunction "2_2") (pintype "passive"))
      (node (ref "LS3") (pin "E") (pinfunction "E_E") (pintype "passive"))
      (node (ref "RS4") (pin "2") (pinfunction "2_2") (pintype "passive"))
      (node (ref "U1") (pin "28") (pinfunction "S20_28") (pintype "passive"))
    )
    (net (code "26") (name "LS4") (class "Default")
      (node (ref "C5") (pin "2") (pinfunction "2_2") (pintype "passive"))
      (node (ref "LS4") (pin "E") (pinfunction "E_E") (pintype "passive"))
      (node (ref "RS5") (pin "2") (pinfunction "2_2") (pintype "passive"))
      (node (ref "U1") (pin "27") (pinfunction "S19_27") (pintype "passive"))
    )
    (net (code "27") (name "LS5") (class "Default")
      (node (ref "C6") (pin "2") (pinfunction "2_2") (pintype "passive"))
      (node (ref "LS5") (pin "E") (pinfunction "E_E") (pintype "passive"))
      (node (ref "RS6") (pin "2") (pinfunction "2_2") (pintype "passive"))
      (node (ref "U1") (pin "26") (pinfunction "S18_26") (pintype "passive"))
    )
    (net (code "28") (name "LS6") (class "Default")
      (node (ref "C7") (pin "2") (pinfunction "2_2") (pintype "passive"))
      (node (ref "LS6") (pin "E") (pinfunction "E_E") (pintype "passive"))
      (node (ref "RS7") (pin "2") (pinfunction "2_2") (pintype "passive"))
      (node (ref "U1") (pin "25") (pinfunction "S17_25") (pintype "passive"))
    )
    (net (code "29") (name "LS7") (class "Default")
      (node (ref "C8") (pin "2") (pinfunction "2_2") (pintype "passive"))
      (node (ref "LS7") (pin "E") (pinfunction "E_E") (pintype "passive"))
      (node (ref "RS8") (pin "2") (pinfunction "2_2") (pintype "passive"))
      (node (ref "U1") (pin "12") (pinfunction "S1_12") (pintype "passive"))
    )
    (net (code "30") (name "LS8") (class "Default")
      (node (ref "C9") (pin "2") (pinfunction "2_2") (pintype "passive"))
      (node (ref "LS8") (pin "E") (pinfunction "E_E") (pintype "passive"))
      (node (ref "RS9") (pin "2") (pinfunction "2_2") (pintype "passive"))
      (node (ref "U1") (pin "11") (pinfunction "S2_11") (pintype "passive"))
    )
    (net (code "31") (name "LS9") (class "Default")
      (node (ref "C10") (pin "2") (pinfunction "2_2") (pintype "passive"))
      (node (ref "LS9") (pin "E") (pinfunction "E_E") (pintype "passive"))
      (node (ref "RS10") (pin "2") (pinfunction "2_2") (pintype "passive"))
      (node (ref "U1") (pin "10") (pinfunction "S3_10") (pintype "passive"))
    )
    (net (code "32") (name "LS10") (class "Default")
      (node (ref "C11") (pin "2") (pinfunction "2_2") (pintype "passive"))
      (node (ref "LS10") (pin "E") (pinfunction "E_E") (pintype "passive"))
      (node (ref "RS11") (pin "2") (pinfunction "2_2") (pintype "passive"))
      (node (ref "U1") (pin "9") (pinfunction "S4_9") (pintype "passive"))
    )
    (net (code "33") (name "LS11") (class "Default")
      (node (ref "C12") (pin "2") (pinfunction "2_2") (pintype "passive"))
      (node (ref "LS11") (pin "E") (pinfunction "E_E") (pintype "passive"))
      (node (ref "RS12") (pin "2") (pinfunction "2_2") (pintype "passive"))
      (node (ref "U1") (pin "8") (pinfunction "S5_8") (pintype "passive"))
    )
    (net (code "34") (name "LS12") (class "Default")
      (node (ref "C13") (pin "2") (pinfunction "2_2") (pintype "passive"))
      (node (ref "LS12") (pin "E") (pinfunction "E_E") (pintype "passive"))
      (node (ref "RS13") (pin "2") (pinfunction "2_2") (pintype "passive"))
      (node (ref "U1") (pin "7") (pinfunction "S6_7") (pintype "passive"))
    )
    (net (code "35") (name "LS13") (class "Default")
      (node (ref "C14") (pin "2") (pinfunction "2_2") (pintype "passive"))
      (node (ref "LS13") (pin "E") (pinfunction "E_E") (pintype "passive"))
      (node (ref "RS14") (pin "2") (pinfunction "2_2") (pintype "passive"))
      (node (ref "U1") (pin "6") (pinfunction "S7_6") (pintype "passive"))
    )
    (net (code "36") (name "LS14") (class "Default")
      (node (ref "C15") (pin "2") (pinfunction "2_2") (pintype "passive"))
      (node (ref "LS14") (pin "E") (pinfunction "E_E") (pintype "passive"))
      (node (ref "RS15") (pin "2") (pinfunction "2_2") (pintype "passive"))
      (node (ref "U1") (pin "5") (pinfunction "S8_5") (pintype "passive"))
    )
    (net (code "37") (name "LS15") (class "Default")
      (node (ref "C16") (pin "2") (pinfunction "2_2") (pintype "passive"))
      (node (ref "LS15") (pin "E") (pinfunction "E_E") (pintype "passive"))
      (node (ref "RS16") (pin "2") (pinfunction "2_2") (pintype "passive"))
      (node (ref "U1") (pin "4") (pinfunction "S9_4") (pintype "passive"))
    )
    (net (code "38") (name "LS16") (class "Default")
      (node (ref "C17") (pin "2") (pinfunction "2_2") (pintype "passive"))
      (node (ref "LS16") (pin "E") (pinfunction "E_E") (pintype "passive"))
      (node (ref "RS17") (pin "2") (pinfunction "2_2") (pintype "passive"))
      (node (ref "U1") (pin "3") (pinfunction "S10_3") (pintype "passive"))
    )
    (net (code "39") (name "LS17") (class "Default")
      (node (ref "C18") (pin "2") (pinfunction "2_2") (pintype "passive"))
      (node (ref "LS17") (pin "E") (pinfunction "E_E") (pintype "passive"))
      (node (ref "RS18") (pin "2") (pinfunction "2_2") (pintype "passive"))
      (node (ref "U1") (pin "2") (pinfunction "S11_2") (pintype "passive"))
    )
    (net (code "40") (name "LS18") (class "Default")
      (node (ref "C19") (pin "2") (pinfunction "2_2") (pintype "passive"))
      (node (ref "LS18") (pin "E") (pinfunction "E_E") (pintype "passive"))
      (node (ref "RS19") (pin "2") (pinfunction "2_2") (pintype "passive"))
      (node (ref "U1") (pin "1") (pinfunction "S12_1") (pintype "passive"))
    )
    (net (code "41") (name "LS19") (class "Default")
      (node (ref "C20") (pin "2") (pinfunction "2_2") (pintype "passive"))
      (node (ref "LS19") (pin "E") (pinfunction "E_E") (pintype "passive"))
      (node (ref "RS20") (pin "2") (pinfunction "2_2") (pintype "passive"))
      (node (ref "U1") (pin "45") (pinfunction "S16_45") (pintype "passive"))
    )
    (net (code "42") (name "LS20") (class "Default")
      (node (ref "C21") (pin "2") (pinfunction "2_2") (pintype "passive"))
      (node (ref "LS20") (pin "E") (pinfunction "E_E") (pintype "passive"))
      (node (ref "RS21") (pin "2") (pinfunction "2_2") (pintype "passive"))
      (node (ref "U1") (pin "46") (pinfunction "S15_46") (pintype "passive"))
    )
    (net (code "43") (name "LS21") (class "Default")
      (node (ref "C22") (pin "2") (pinfunction "2_2") (pintype "passive"))
      (node (ref "LS21") (pin "E") (pinfunction "E_E") (pintype "passive"))
      (node (ref "RS22") (pin "2") (pinfunction "2_2") (pintype "passive"))
      (node (ref "U1") (pin "47") (pinfunction "S14_47") (pintype "passive"))
    )
    (net (code "44") (name "LS22") (class "Default")
      (node (ref "C23") (pin "2") (pinfunction "2_2") (pintype "passive"))
      (node (ref "LS22") (pin "E") (pinfunction "E_E") (pintype "passive"))
      (node (ref "RS23") (pin "2") (pinfunction "2_2") (pintype "passive"))
      (node (ref "U1") (pin "48") (pinfunction "S13_48") (pintype "passive"))
    )
    (net (code "45") (name "LS23") (class "Default")
      (node (ref "C24") (pin "2") (pinfunction "2_2") (pintype "passive"))
      (node (ref "LS23") (pin "E") (pinfunction "E_E") (pintype "passive"))
      (node (ref "RS24") (pin "2") (pinfunction "2_2") (pintype "passive"))
      (node (ref "U1") (pin "40") (pinfunction "S32_40") (pintype "passive"))
    )
    (net (code "46") (name "LS24") (class "Default")
      (node (ref "C25") (pin "2") (pinfunction "2_2") (pintype "passive"))
      (node (ref "LS24") (pin "E") (pinfunction "E_E") (pintype "passive"))
      (node (ref "RS25") (pin "2") (pinfunction "2_2") (pintype "passive"))
      (node (ref "U1") (pin "37") (pinfunction "S29_37") (pintype "passive"))
    )
    (net (code "47") (name "LS25") (class "Default")
      (node (ref "C26") (pin "2") (pinfunction "2_2") (pintype "passive"))
      (node (ref "LS25") (pin "E") (pinfunction "E_E") (pintype "passive"))
      (node (ref "RS26") (pin "2") (pinfunction "2_2") (pintype "passive"))
      (node (ref "U1") (pin "38") (pinfunction "S30_38") (pintype "passive"))
    )
    (net (code "48") (name "LS26") (class "Default")
      (node (ref "C27") (pin "2") (pinfunction "2_2") (pintype "passive"))
      (node (ref "LS26") (pin "E") (pinfunction "E_E") (pintype "passive"))
      (node (ref "RS27") (pin "2") (pinfunction "2_2") (pintype "passive"))
      (node (ref "U1") (pin "39") (pinfunction "S31_39") (pintype "passive"))
    )
    (net (code "49") (name "LS27") (class "Default")
      (node (ref "C28") (pin "2") (pinfunction "2_2") (pintype "passive"))
      (node (ref "LS27") (pin "E") (pinfunction "E_E") (pintype "passive"))
      (node (ref "RS28") (pin "2") (pinfunction "2_2") (pintype "passive"))
      (node (ref "U1") (pin "36") (pinfunction "S28_36") (pintype "passive"))
    )
    (net (code "50") (name "LS28") (class "Default")
      (node (ref "C29") (pin "2") (pinfunction "2_2") (pintype "passive"))
      (node (ref "LS28") (pin "E") (pinfunction "E_E") (pintype "passive"))
      (node (ref "RS29") (pin "2") (pinfunction "2_2") (pintype "passive"))
      (node (ref "U1") (pin "35") (pinfunction "S27_35") (pintype "passive"))
    )
    (net (code "51") (name "LS29") (class "Default")
      (node (ref "C30") (pin "2") (pinfunction "2_2") (pintype "passive"))
      (node (ref "LS29") (pin "E") (pinfunction "E_E") (pintype "passive"))
      (node (ref "RS30") (pin "2") (pinfunction "2_2") (pintype "passive"))
      (node (ref "U1") (pin "34") (pinfunction "S26_34") (pintype "passive"))
    )
    (net (code "52") (name "LS30") (class "Default")
      (node (ref "C31") (pin "2") (pinfunction "2_2") (pintype "passive"))
      (node (ref "LS30") (pin "E") (pinfunction "E_E") (pintype "passive"))
      (node (ref "RS31") (pin "2") (pinfunction "2_2") (pintype "passive"))
      (node (ref "U1") (pin "33") (pinfunction "S25_33") (pintype "passive"))
    )
    (net (code "53") (name "LS31") (class "Default")
      (node (ref "C32") (pin "2") (pinfunction "2_2") (pintype "passive"))
      (node (ref "LS31") (pin "E") (pinfunction "E_E") (pintype "passive"))
      (node (ref "RS32") (pin "2") (pinfunction "2_2") (pintype "passive"))
      (node (ref "U1") (pin "32") (pinfunction "S24_32") (pintype "passive"))
    )
    (net (code "54") (name "Net-(BOOSTER-3)") (class "Default")
      (node (ref "BOOSTER") (pin "P3") (pinfunction "3_P3") (pintype "bidirectional"))
      (node (ref "D") (pin "A") (pinfunction "A_A") (pintype "passive"))
    )
    (net (code "55") (name "Net-(D-PadC)") (class "Default")
      (node (ref "D") (pin "C") (pinfunction "C_C") (pintype "passive"))
      (node (ref "R4") (pin "2") (pinfunction "2_2") (pintype "passive"))
    )
    (net (code "56") (name "Net-(LED0-PadA)") (class "Default")
      (node (ref "LED0") (pin "A") (pinfunction "A_A") (pintype "passive"))
      (node (ref "RL1") (pin "1") (pinfunction "1_1") (pintype "passive"))
    )
    (net (code "57") (name "Net-(LED1-PadA)") (class "Default")
      (node (ref "LED1") (pin "A") (pinfunction "A_A") (pintype "passive"))
      (node (ref "RL2") (pin "1") (pinfunction "1_1") (pintype "passive"))
    )
    (net (code "58") (name "Net-(LED2-PadA)") (class "Default")
      (node (ref "LED2") (pin "A") (pinfunction "A_A") (pintype "passive"))
      (node (ref "RL3") (pin "1") (pinfunction "1_1") (pintype "passive"))
    )
    (net (code "59") (name "Net-(LED3-PadA)") (class "Default")
      (node (ref "LED3") (pin "A") (pinfunction "A_A") (pintype "passive"))
      (node (ref "RL4") (pin "1") (pinfunction "1_1") (pintype "passive"))
    )
    (net (code "60") (name "Net-(LED4-PadA)") (class "Default")
      (node (ref "LED4") (pin "A") (pinfunction "A_A") (pintype "passive"))
      (node (ref "RL5") (pin "1") (pinfunction "1_1") (pintype "passive"))
    )
    (net (code "61") (name "Net-(LED5-PadA)") (class "Default")
      (node (ref "LED5") (pin "A") (pinfunction "A_A") (pintype "passive"))
      (node (ref "RL6") (pin "1") (pinfunction "1_1") (pintype "passive"))
    )
    (net (code "62") (name "Net-(LED6-PadA)") (class "Default")
      (node (ref "LED6") (pin "A") (pinfunction "A_A") (pintype "passive"))
      (node (ref "RL7") (pin "1") (pinfunction "1_1") (pintype "passive"))
    )
    (net (code "63") (name "Net-(LED7-PadA)") (class "Default")
      (node (ref "LED7") (pin "A") (pinfunction "A_A") (pintype "passive"))
      (node (ref "RL8") (pin "1") (pinfunction "1_1") (pintype "passive"))
    )
    (net (code "64") (name "Net-(LED8-PadA)") (class "Default")
      (node (ref "LED8") (pin "A") (pinfunction "A_A") (pintype "passive"))
      (node (ref "RL9") (pin "1") (pinfunction "1_1") (pintype "passive"))
    )
    (net (code "65") (name "Net-(LED9-PadA)") (class "Default")
      (node (ref "LED9") (pin "A") (pinfunction "A_A") (pintype "passive"))
      (node (ref "RL10") (pin "1") (pinfunction "1_1") (pintype "passive"))
    )
    (net (code "66") (name "Net-(LED10-PadA)") (class "Default")
      (node (ref "LED10") (pin "A") (pinfunction "A_A") (pintype "passive"))
      (node (ref "RL11") (pin "1") (pinfunction "1_1") (pintype "passive"))
    )
    (net (code "67") (name "Net-(LED11-PadA)") (class "Default")
      (node (ref "LED11") (pin "A") (pinfunction "A_A") (pintype "passive"))
      (node (ref "RL12") (pin "1") (pinfunction "1_1") (pintype "passive"))
    )
    (net (code "68") (name "Net-(LED12-PadA)") (class "Default")
      (node (ref "LED12") (pin "A") (pinfunction "A_A") (pintype "passive"))
      (node (ref "RL13") (pin "1") (pinfunction "1_1") (pintype "passive"))
    )
    (net (code "69") (name "Net-(LED13-PadA)") (class "Default")
      (node (ref "LED13") (pin "A") (pinfunction "A_A") (pintype "passive"))
      (node (ref "RL14") (pin "1") (pinfunction "1_1") (pintype "passive"))
    )
    (net (code "70") (name "Net-(LED14-PadA)") (class "Default")
      (node (ref "LED14") (pin "A") (pinfunction "A_A") (pintype "passive"))
      (node (ref "RL15") (pin "1") (pinfunction "1_1") (pintype "passive"))
    )
    (net (code "71") (name "Net-(LED15-PadA)") (class "Default")
      (node (ref "LED15") (pin "A") (pinfunction "A_A") (pintype "passive"))
      (node (ref "RL16") (pin "1") (pinfunction "1_1") (pintype "passive"))
    )
    (net (code "72") (name "Net-(LED16-PadA)") (class "Default")
      (node (ref "LED16") (pin "A") (pinfunction "A_A") (pintype "passive"))
      (node (ref "RL17") (pin "1") (pinfunction "1_1") (pintype "passive"))
    )
    (net (code "73") (name "Net-(LED17-PadA)") (class "Default")
      (node (ref "LED17") (pin "A") (pinfunction "A_A") (pintype "passive"))
      (node (ref "RL18") (pin "1") (pinfunction "1_1") (pintype "passive"))
    )
    (net (code "74") (name "Net-(LED18-PadA)") (class "Default")
      (node (ref "LED18") (pin "A") (pinfunction "A_A") (pintype "passive"))
      (node (ref "RL19") (pin "1") (pinfunction "1_1") (pintype "passive"))
    )
    (net (code "75") (name "Net-(LED19-PadA)") (class "Default")
      (node (ref "LED19") (pin "A") (pinfunction "A_A") (pintype "passive"))
      (node (ref "RL20") (pin "1") (pinfunction "1_1") (pintype "passive"))
    )
    (net (code "76") (name "Net-(LED20-PadA)") (class "Default")
      (node (ref "LED20") (pin "A") (pinfunction "A_A") (pintype "passive"))
      (node (ref "RL21") (pin "1") (pinfunction "1_1") (pintype "passive"))
    )
    (net (code "77") (name "Net-(LED21-PadA)") (class "Default")
      (node (ref "LED21") (pin "A") (pinfunction "A_A") (pintype "passive"))
      (node (ref "RL22") (pin "1") (pinfunction "1_1") (pintype "passive"))
    )
    (net (code "78") (name "Net-(LED22-PadA)") (class "Default")
      (node (ref "LED22") (pin "A") (pinfunction "A_A") (pintype "passive"))
      (node (ref "RL23") (pin "1") (pinfunction "1_1") (pintype "passive"))
    )
    (net (code "79") (name "Net-(LED23-PadA)") (class "Default")
      (node (ref "LED23") (pin "A") (pinfunction "A_A") (pintype "passive"))
      (node (ref "RL24") (pin "1") (pinfunction "1_1") (pintype "passive"))
    )
    (net (code "80") (name "Net-(LED24-PadA)") (class "Default")
      (node (ref "LED24") (pin "A") (pinfunction "A_A") (pintype "passive"))
      (node (ref "RL25") (pin "1") (pinfunction "1_1") (pintype "passive"))
    )
    (net (code "81") (name "Net-(LED25-PadA)") (class "Default")
      (node (ref "LED25") (pin "A") (pinfunction "A_A") (pintype "passive"))
      (node (ref "RL26") (pin "1") (pinfunction "1_1") (pintype "passive"))
    )
    (net (code "82") (name "Net-(LED26-PadA)") (class "Default")
      (node (ref "LED26") (pin "A") (pinfunction "A_A") (pintype "passive"))
      (node (ref "RL27") (pin "1") (pinfunction "1_1") (pintype "passive"))
    )
    (net (code "83") (name "Net-(LED27-PadA)") (class "Default")
      (node (ref "LED27") (pin "A") (pinfunction "A_A") (pintype "passive"))
      (node (ref "RL28") (pin "1") (pinfunction "1_1") (pintype "passive"))
    )
    (net (code "84") (name "Net-(LED28-PadA)") (class "Default")
      (node (ref "LED28") (pin "A") (pinfunction "A_A") (pintype "passive"))
      (node (ref "RL29") (pin "1") (pinfunction "1_1") (pintype "passive"))
    )
    (net (code "85") (name "Net-(LED29-PadA)") (class "Default")
      (node (ref "LED29") (pin "A") (pinfunction "A_A") (pintype "passive"))
      (node (ref "RL30") (pin "1") (pinfunction "1_1") (pintype "passive"))
    )
    (net (code "86") (name "Net-(LED30-PadA)") (class "Default")
      (node (ref "LED30") (pin "A") (pinfunction "A_A") (pintype "passive"))
      (node (ref "RL31") (pin "1") (pinfunction "1_1") (pintype "passive"))
    )
    (net (code "87") (name "Net-(LED31-PadA)") (class "Default")
      (node (ref "LED31") (pin "A") (pinfunction "A_A") (pintype "passive"))
      (node (ref "RL32") (pin "1") (pinfunction "1_1") (pintype "passive"))
    )
    (net (code "88") (name "Net-(Q1-G)") (class "Default")
      (node (ref "Q1") (pin "2") (pinfunction "G_2") (pintype "passive"))
      (node (ref "R1") (pin "P$2") (pinfunction "2_P$2") (pintype "passive"))
    )
    (net (code "89") (name "Net-(R3-2)") (class "Default")
      (node (ref "C65") (pin "+") (pinfunction "+_+") (pintype "passive"))
      (node (ref "K1") (pin "P") (pinfunction "P_P") (pintype "passive"))
      (node (ref "R3") (pin "P$2") (pinfunction "2_P$2") (pintype "passive"))
    )
    (net (code "90") (name "VCC") (class "Default")
      (node (ref "K1") (pin "O") (pinfunction "O_O") (pintype "passive"))
      (node (ref "R4") (pin "1") (pinfunction "1_1") (pintype "passive"))
    )
    (net (code "91") (name "unconnected-(BOOSTER-2-PadP2)") (class "Default")
      (node (ref "BOOSTER") (pin "P2") (pinfunction "2_P2") (pintype "bidirectional"))
    )
    (net (code "92") (name "unconnected-(LRFE-Pad5)") (class "Default")
      (node (ref "LRFE") (pin "5") (pinfunction "5_5") (pintype "passive"))
    )
    (net (code "93") (name "unconnected-(LRFE-Pad6)") (class "Default")
      (node (ref "LRFE") (pin "6") (pinfunction "6_6") (pintype "passive"))
    )
    (net (code "94") (name "unconnected-(LRFN-Pad5)") (class "Default")
      (node (ref "LRFN") (pin "5") (pinfunction "5_5") (pintype "passive"))
    )
    (net (code "95") (name "unconnected-(LRFN-Pad6)") (class "Default")
      (node (ref "LRFN") (pin "6") (pinfunction "6_6") (pintype "passive"))
    )
    (net (code "96") (name "unconnected-(LRFS-Pad5)") (class "Default")
      (node (ref "LRFS") (pin "5") (pinfunction "5_5") (pintype "passive"))
    )
    (net (code "97") (name "unconnected-(LRFS-Pad6)") (class "Default")
      (node (ref "LRFS") (pin "6") (pinfunction "6_6") (pintype "passive"))
    )
    (net (code "98") (name "unconnected-(LRFW-Pad5)") (class "Default")
      (node (ref "LRFW") (pin "5") (pinfunction "5_5") (pintype "passive"))
    )
    (net (code "99") (name "unconnected-(LRFW-Pad6)") (class "Default")
      (node (ref "LRFW") (pin "6") (pinfunction "6_6") (pintype "passive"))
    )
    (net (code "100") (name "unconnected-(SOLENOID-2-PadP2)") (class "Default")
      (node (ref "SOLENOID") (pin "P2") (pinfunction "2_P2") (pintype "bidirectional"))
    )
    (net (code "101") (name "unconnected-(U1-NC-Pad44)") (class "Default")
      (node (ref "U1") (pin "44") (pinfunction "NC_44") (pintype "passive"))
    )
    (net (code "102") (name "unconnected-(U1-NC_2-Pad41)") (class "Default")
      (node (ref "U1") (pin "41") (pinfunction "NC_2_41") (pintype "passive"))
    )
    (net (code "103") (name "unconnected-(U1-NC_3-Pad42)") (class "Default")
      (node (ref "U1") (pin "42") (pinfunction "NC_3_42") (pintype "passive"))
    )
  )
)
